# sensorAA.net
KiCad netlist of a schematic drawn in EAGLE
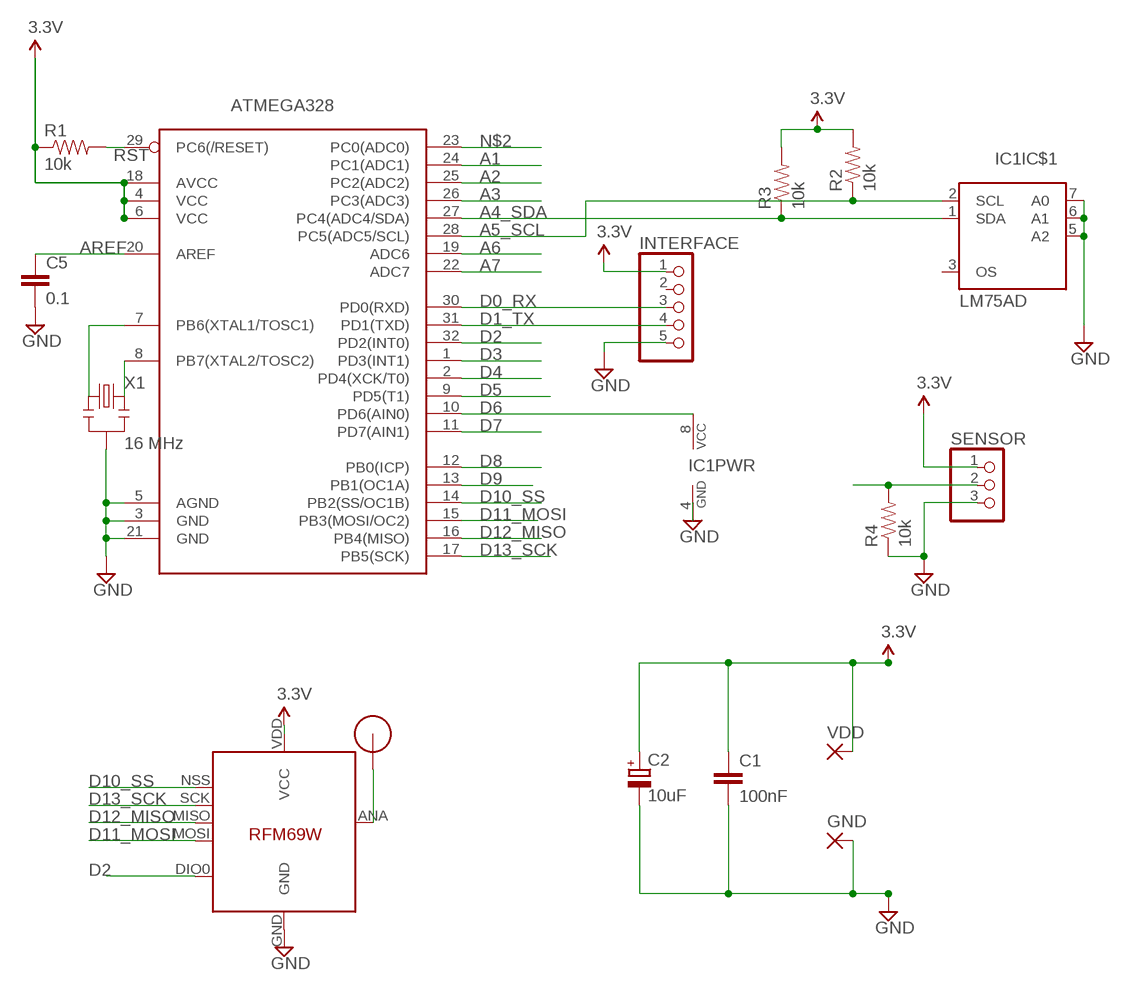
[diagram p0: schematic, sheet 1]

(export (version "E")
  (design (tool "Eeschema 10.0.6"))
  (components
    (comp (ref "ATMEGA328")
      (value "ATMega-328")
      (footprint "eagle-import:TQFP32-08")
      (libsource (lib "eagle-import") (part "ATMEGA168/328TQFP32"))
    )
    (comp (ref "C1")
      (value "100nF")
      (footprint "eagle-import:C2012")
      (libsource (lib "eagle-import") (part "C-EUC2012"))
    )
    (comp (ref "C2")
      (value "10uF")
      (footprint "eagle-import:SMC_A")
      (libsource (lib "eagle-import") (part "CPOL-EUSMCA"))
    )
    (comp (ref "C5")
      (value "0.1")
      (footprint "eagle-import:0603-CAP")
      (libsource (lib "eagle-import") (part "CAP0603-CAP"))
    )
    (comp (ref "GND")
      (value "SMD5")
      (footprint "eagle-import:SMD2,54-5,08")
      (libsource (lib "eagle-import") (part "SMD5"))
    )
    (comp (ref "IC1")
      (value "LM75AD")
      (footprint "eagle-import:SO08")
      (libsource (lib "eagle-import") (part "LM75AD"))
    )
    (comp (ref "IC4")
      (value "RFM69")
      (footprint "eagle-import:RFM69W-MINPADS")
      (libsource (lib "eagle-import") (part "RFM69"))
    )
    (comp (ref "INTERFACE")
      (value "PINHD-1X5")
      (footprint "eagle-import:1X05")
      (libsource (lib "eagle-import") (part "PINHD-1X5"))
    )
    (comp (ref "R1")
      (value "10k")
      (footprint "eagle-import:0603-RES")
      (libsource (lib "eagle-import") (part "RESISTOR0603-RES"))
    )
    (comp (ref "R2")
      (value "10k")
      (footprint "eagle-import:0603-RES")
      (libsource (lib "eagle-import") (part "RESISTOR0603-RES"))
    )
    (comp (ref "R3")
      (value "10k")
      (footprint "eagle-import:0603-RES")
      (libsource (lib "eagle-import") (part "RESISTOR0603-RES"))
    )
    (comp (ref "R4")
      (value "10k")
      (footprint "eagle-import:0603-RES")
      (libsource (lib "eagle-import") (part "RESISTOR0603-RES"))
    )
    (comp (ref "SENSOR")
      (value "PINHD-1X3")
      (footprint "eagle-import:1X03")
      (libsource (lib "eagle-import") (part "PINHD-1X3"))
    )
    (comp (ref "U$1")
      (value "RFM12B_ANTENNA")
      (footprint "eagle-import:RFM12B-ANTENNA")
      (libsource (lib "eagle-import") (part "RFM12B_ANTENNA"))
    )
    (comp (ref "VDD")
      (value "SMD5")
      (footprint "eagle-import:SMD2,54-5,08")
      (libsource (lib "eagle-import") (part "SMD5"))
    )
    (comp (ref "X1")
      (value "16 MHz")
      (footprint "eagle-import:RESONATOR-SMD")
      (libsource (lib "eagle-import") (part "RESONATORSMD"))
    )
  )
  (nets
    (net (code "1") (name "/A1") (class "Default")
      (node (ref "ATMEGA328") (pin "24") (pinfunction "PC1(ADC1)_24") (pintype "bidirectional"))
    )
    (net (code "2") (name "/A2") (class "Default")
      (node (ref "ATMEGA328") (pin "25") (pinfunction "PC2(ADC2)_25") (pintype "bidirectional"))
    )
    (net (code "3") (name "/A3") (class "Default")
      (node (ref "ATMEGA328") (pin "26") (pinfunction "PC3(ADC3)_26") (pintype "bidirectional"))
    )
    (net (code "4") (name "/A4_SDA") (class "Default")
      (node (ref "ATMEGA328") (pin "27") (pinfunction "PC4(ADC4/SDA)_27") (pintype "bidirectional"))
      (node (ref "IC1") (pin "1") (pinfunction "SDA_1") (pintype "bidirectional"))
      (node (ref "R3") (pin "1") (pinfunction "1_1") (pintype "passive"))
    )
    (net (code "5") (name "/A5_SCL") (class "Default")
      (node (ref "ATMEGA328") (pin "28") (pinfunction "PC5(ADC5/SCL)_28") (pintype "bidirectional"))
      (node (ref "IC1") (pin "2") (pinfunction "SCL_2") (pintype "input"))
      (node (ref "R2") (pin "1") (pinfunction "1_1") (pintype "passive"))
    )
    (net (code "6") (name "/A6") (class "Default")
      (node (ref "ATMEGA328") (pin "19") (pinfunction "ADC6_19") (pintype "bidirectional"))
    )
    (net (code "7") (name "/A7") (class "Default")
      (node (ref "ATMEGA328") (pin "22") (pinfunction "ADC7_22") (pintype "bidirectional"))
    )
    (net (code "8") (name "/AREF") (class "Default")
      (node (ref "ATMEGA328") (pin "20") (pinfunction "AREF_20") (pintype "bidirectional"))
      (node (ref "C5") (pin "1") (pinfunction "1_1") (pintype "passive"))
    )
    (net (code "9") (name "/D0_RX") (class "Default")
      (node (ref "ATMEGA328") (pin "30") (pinfunction "PD0(RXD)_30") (pintype "bidirectional"))
      (node (ref "INTERFACE") (pin "3") (pinfunction "3_3") (pintype "passive"))
    )
    (net (code "10") (name "/D1_TX") (class "Default")
      (node (ref "ATMEGA328") (pin "31") (pinfunction "PD1(TXD)_31") (pintype "bidirectional"))
      (node (ref "INTERFACE") (pin "4") (pinfunction "4_4") (pintype "passive"))
    )
    (net (code "11") (name "/D2") (class "Default")
      (node (ref "ATMEGA328") (pin "32") (pinfunction "PD2(INT0)_32") (pintype "bidirectional"))
      (node (ref "IC4") (pin "DIO0") (pinfunction "DIO0_DIO0") (pintype "open_collector"))
    )
    (net (code "12") (name "/D3") (class "Default")
      (node (ref "ATMEGA328") (pin "1") (pinfunction "PD3(INT1)_1") (pintype "bidirectional"))
      (node (ref "R4") (pin "2") (pinfunction "2_2") (pintype "passive"))
      (node (ref "SENSOR") (pin "2") (pinfunction "2_2") (pintype "passive"))
    )
    (net (code "13") (name "/D4") (class "Default")
      (node (ref "ATMEGA328") (pin "2") (pinfunction "PD4(XCK/T0)_2") (pintype "bidirectional"))
    )
    (net (code "14") (name "/D5") (class "Default")
      (node (ref "ATMEGA328") (pin "9") (pinfunction "PD5(T1)_9") (pintype "bidirectional"))
    )
    (net (code "15") (name "/D6") (class "Default")
      (node (ref "ATMEGA328") (pin "10") (pinfunction "PD6(AIN0)_10") (pintype "bidirectional"))
      (node (ref "IC1") (pin "8") (pinfunction "VCC_8") (pintype "power_in"))
    )
    (net (code "16") (name "/D7") (class "Default")
      (node (ref "ATMEGA328") (pin "11") (pinfunction "PD7(AIN1)_11") (pintype "bidirectional"))
    )
    (net (code "17") (name "/D8") (class "Default")
      (node (ref "ATMEGA328") (pin "12") (pinfunction "PB0(ICP)_12") (pintype "bidirectional"))
    )
    (net (code "18") (name "/D9") (class "Default")
      (node (ref "ATMEGA328") (pin "13") (pinfunction "PB1(OC1A)_13") (pintype "bidirectional"))
    )
    (net (code "19") (name "/D10_SS") (class "Default")
      (node (ref "ATMEGA328") (pin "14") (pinfunction "PB2(SS/OC1B)_14") (pintype "bidirectional"))
      (node (ref "IC4") (pin "NSS") (pinfunction "SEL_NSS") (pintype "input"))
    )
    (net (code "20") (name "/D11_MOSI") (class "Default")
      (node (ref "ATMEGA328") (pin "15") (pinfunction "PB3(MOSI/OC2)_15") (pintype "bidirectional"))
      (node (ref "IC4") (pin "MOSI") (pinfunction "MOSI_MOSI") (pintype "output"))
    )
    (net (code "21") (name "/D12_MISO") (class "Default")
      (node (ref "ATMEGA328") (pin "16") (pinfunction "PB4(MISO)_16") (pintype "bidirectional"))
      (node (ref "IC4") (pin "MISO") (pinfunction "MISO_MISO") (pintype "input"))
    )
    (net (code "22") (name "/D13_SCK") (class "Default")
      (node (ref "ATMEGA328") (pin "17") (pinfunction "PB5(SCK)_17") (pintype "bidirectional"))
      (node (ref "IC4") (pin "SCK") (pinfunction "SCK_SCK") (pintype "input"))
    )
    (net (code "23") (name "/N$2") (class "Default")
      (node (ref "ATMEGA328") (pin "23") (pinfunction "PC0(ADC0)_23") (pintype "bidirectional"))
    )
    (net (code "24") (name "/RST") (class "Default")
      (node (ref "ATMEGA328") (pin "29") (pinfunction "PC6(/RESET)_29") (pintype "bidirectional"))
      (node (ref "R1") (pin "2") (pinfunction "2_2") (pintype "passive"))
    )
    (net (code "25") (name "3.3V") (class "Default")
      (node (ref "ATMEGA328") (pin "18") (pinfunction "AVCC_18") (pintype "bidirectional"))
      (node (ref "ATMEGA328") (pin "4") (pinfunction "VCC_4") (pintype "bidirectional"))
      (node (ref "ATMEGA328") (pin "6") (pinfunction "VCC_6") (pintype "bidirectional"))
      (node (ref "C1") (pin "1") (pinfunction "1_1") (pintype "passive"))
      (node (ref "C2") (pin "+") (pinfunction "+_+") (pintype "passive"))
      (node (ref "IC4") (pin "VDD") (pinfunction "VCC_VDD") (pintype "power_in"))
      (node (ref "INTERFACE") (pin "1") (pinfunction "1_1") (pintype "passive"))
      (node (ref "R1") (pin "1") (pinfunction "1_1") (pintype "passive"))
      (node (ref "R2") (pin "2") (pinfunction "2_2") (pintype "passive"))
      (node (ref "R3") (pin "2") (pinfunction "2_2") (pintype "passive"))
      (node (ref "SENSOR") (pin "1") (pinfunction "1_1") (pintype "passive"))
      (node (ref "VDD") (pin "1") (pinfunction "P_1") (pintype "passive"))
    )
    (net (code "26") (name "GND") (class "Default")
      (node (ref "ATMEGA328") (pin "21") (pinfunction "GND_21") (pintype "bidirectional"))
      (node (ref "ATMEGA328") (pin "3") (pinfunction "GND_3") (pintype "bidirectional"))
      (node (ref "ATMEGA328") (pin "5") (pinfunction "AGND_5") (pintype "bidirectional"))
      (node (ref "C1") (pin "2") (pinfunction "2_2") (pintype "passive"))
      (node (ref "C2") (pin "-") (pinfunction "-_-") (pintype "passive"))
      (node (ref "C5") (pin "2") (pinfunction "2_2") (pintype "passive"))
      (node (ref "GND") (pin "1") (pinfunction "P_1") (pintype "passive"))
      (node (ref "IC1") (pin "4") (pinfunction "GND_4") (pintype "power_in"))
      (node (ref "IC1") (pin "5") (pinfunction "A2_5") (pintype "input"))
      (node (ref "IC1") (pin "6") (pinfunction "A1_6") (pintype "input"))
      (node (ref "IC1") (pin "7") (pinfunction "A0_7") (pintype "input"))
      (node (ref "IC4") (pin "GND") (pinfunction "GND_GND") (pintype "power_in"))
      (node (ref "INTERFACE") (pin "5") (pinfunction "5_5") (pintype "passive"))
      (node (ref "R4") (pin "1") (pinfunction "1_1") (pintype "passive"))
      (node (ref "SENSOR") (pin "3") (pinfunction "3_3") (pintype "passive"))
      (node (ref "X1") (pin "2") (pinfunction "2_2") (pintype "passive"))
    )
    (net (code "27") (name "Net-(ATMEGA328-PB6(XTAL1{slash}TOSC1))") (class "Default")
      (node (ref "ATMEGA328") (pin "7") (pinfunction "PB6(XTAL1/TOSC1)_7") (pintype "bidirectional"))
      (node (ref "X1") (pin "1") (pinfunction "1_1") (pintype "passive"))
    )
    (net (code "28") (name "Net-(ATMEGA328-PB7(XTAL2{slash}TOSC2))") (class "Default")
      (node (ref "ATMEGA328") (pin "8") (pinfunction "PB7(XTAL2/TOSC2)_8") (pintype "bidirectional"))
      (node (ref "X1") (pin "3") (pinfunction "3_3") (pintype "passive"))
    )
    (net (code "29") (name "Net-(IC4-ANT)") (class "Default")
      (node (ref "IC4") (pin "ANA") (pinfunction "ANT_ANA") (pintype "passive"))
      (node (ref "U$1") (pin "P$1") (pinfunction "1_P$1") (pintype "bidirectional"))
    )
    (net (code "30") (name "unconnected-(IC1A-OS-Pad3)") (class "Default")
      (node (ref "IC1") (pin "3") (pinfunction "OS_3") (pintype "output"))
    )
    (net (code "31") (name "unconnected-(INTERFACE-Pad2)") (class "Default")
      (node (ref "INTERFACE") (pin "2") (pinfunction "2_2") (pintype "passive"))
    )
  )
)
